# Output.net
KiCad netlist of a schematic drawn in Altium Designer
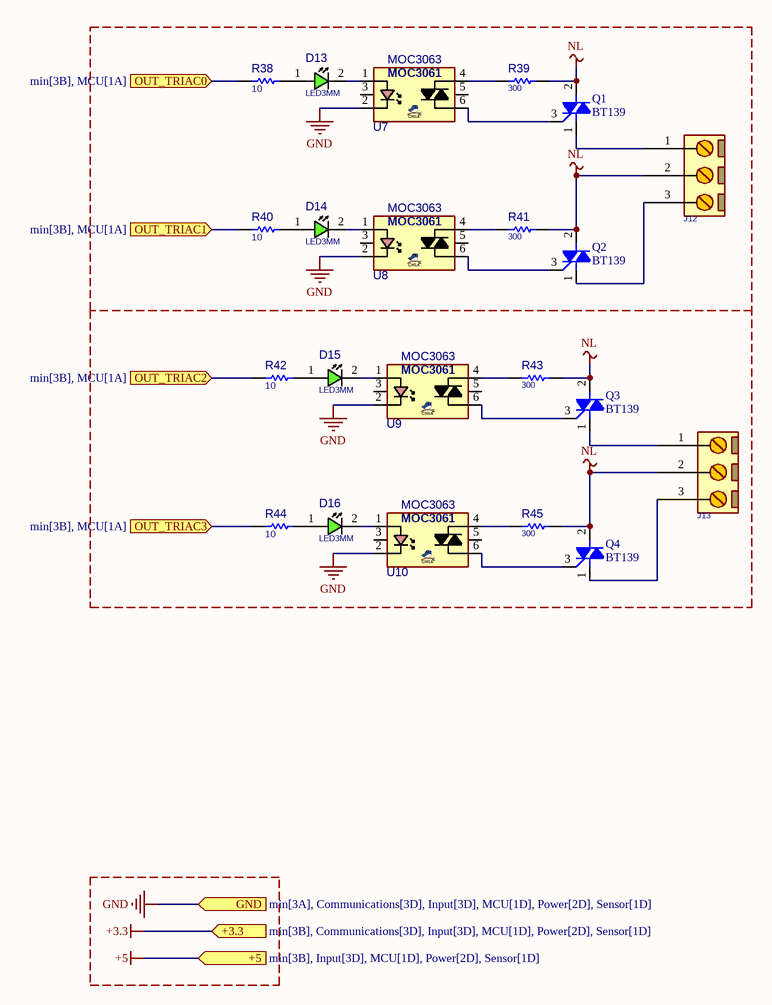
[diagram p0: Output.SchDoc]

(export (version "E")
  (design (tool "Eeschema 10.0.6"))
  (components
    (comp (ref "D13")
      (value "LED3MM")
      (footprint "LED3MM")
      (description "LED, THD, 3MM, GREEN")
      (fields (field (name "MANF") "MANF") (field (name "MANF_P#") "MANF_PART#"))
      (libsource (lib "led(diode)") (part "LED_THD_3MM"))
    )
    (comp (ref "D14")
      (value "LED3MM")
      (footprint "LED3MM")
      (description "LED, THD, 3MM, GREEN")
      (fields (field (name "MANF") "MANF") (field (name "MANF_P#") "MANF_PART#"))
      (libsource (lib "led(diode)") (part "LED_THD_3MM"))
    )
    (comp (ref "D15")
      (value "LED3MM")
      (footprint "LED3MM")
      (description "LED, THD, 3MM, GREEN")
      (fields (field (name "MANF") "MANF") (field (name "MANF_P#") "MANF_PART#"))
      (libsource (lib "led(diode)") (part "LED_THD_3MM"))
    )
    (comp (ref "D16")
      (value "LED3MM")
      (footprint "LED3MM")
      (description "LED, THD, 3MM, GREEN")
      (fields (field (name "MANF") "MANF") (field (name "MANF_P#") "MANF_PART#"))
      (libsource (lib "led(diode)") (part "LED_THD_3MM"))
    )
    (comp (ref "J12")
      (value "CONN_GMSTB3")
      (footprint "GMSTB762_3")
      (description "CONN, PHOENIX MSTB, 5-G, 5.08mm pitch")
      (fields (field (name "MANF_P#") "GMSTB 2,5/3-G-7,62"))
      (libsource (lib "conn_terminalB") (part "CONN_GMSTB762_3"))
    )
    (comp (ref "J13")
      (value "CONN_GMSTB3")
      (footprint "GMSTB762_3")
      (description "CONN, PHOENIX MSTB, 5-G, 5.08mm pitch")
      (fields (field (name "MANF_P#") "GMSTB 2,5/3-G-7,62"))
      (libsource (lib "conn_terminalB") (part "CONN_GMSTB762_3"))
    )
    (comp (ref "Q1")
      (value "BT139")
      (footprint "TO220_3")
      (description "Triac, 600V, 4A, TO-220, Silicon Bidirectional Thyristor")
      (libsource (lib "triac_diac") (part "TRIAC"))
    )
    (comp (ref "Q2")
      (value "BT139")
      (footprint "TO220_3")
      (description "Triac, 600V, 4A, TO-220, Silicon Bidirectional Thyristor")
      (libsource (lib "triac_diac") (part "TRIAC"))
    )
    (comp (ref "Q3")
      (value "BT139")
      (footprint "TO220_3")
      (description "Triac, 600V, 4A, TO-220, Silicon Bidirectional Thyristor")
      (libsource (lib "triac_diac") (part "TRIAC"))
    )
    (comp (ref "Q4")
      (value "BT139")
      (footprint "TO220_3")
      (description "Triac, 600V, 4A, TO-220, Silicon Bidirectional Thyristor")
      (libsource (lib "triac_diac") (part "TRIAC"))
    )
    (comp (ref "R38")
      (value "10")
      (footprint "R1206")
      (description "RESISTOR, SMD")
      (libsource (lib "passive_smd") (part "RES_SMD"))
    )
    (comp (ref "R39")
      (value "300")
      (footprint "R025W_AX_VER")
      (description "RESISTOR, THD")
      (fields (field (name "MANF_P#") "RK73H1ETTP4701F") (field (name "MANF") "KOA SPEER"))
      (libsource (lib "passive_thd") (part "RES_THD"))
    )
    (comp (ref "R40")
      (value "10")
      (footprint "R1206")
      (description "RESISTOR, SMD")
      (libsource (lib "passive_smd") (part "RES_SMD"))
    )
    (comp (ref "R41")
      (value "300")
      (footprint "R025W_AX_VER")
      (description "RESISTOR, THD")
      (fields (field (name "MANF_P#") "RK73H1ETTP4701F") (field (name "MANF") "KOA SPEER"))
      (libsource (lib "passive_thd") (part "RES_THD"))
    )
    (comp (ref "R42")
      (value "10")
      (footprint "R1206")
      (description "RESISTOR, SMD")
      (libsource (lib "passive_smd") (part "RES_SMD"))
    )
    (comp (ref "R43")
      (value "300")
      (footprint "R025W_AX_VER")
      (description "RESISTOR, THD")
      (fields (field (name "MANF_P#") "RK73H1ETTP4701F") (field (name "MANF") "KOA SPEER"))
      (libsource (lib "passive_thd") (part "RES_THD"))
    )
    (comp (ref "R44")
      (value "10")
      (footprint "R1206")
      (description "RESISTOR, SMD")
      (libsource (lib "passive_smd") (part "RES_SMD"))
    )
    (comp (ref "R45")
      (value "300")
      (footprint "R025W_AX_VER")
      (description "RESISTOR, THD")
      (fields (field (name "MANF_P#") "RK73H1ETTP4701F") (field (name "MANF") "KOA SPEER"))
      (libsource (lib "passive_thd") (part "RES_THD"))
    )
    (comp (ref "U7")
      (value "MOC3063")
      (footprint "DIP_6")
      (description "OPTOTRIAC, 600v/1A, 6v In")
      (fields (field (name "MANF_P#") "MOC3061"))
      (libsource (lib "optocoupler") (part "OPT_TRIAC6P_MOC3061"))
    )
    (comp (ref "U8")
      (value "MOC3063")
      (footprint "DIP_6")
      (description "OPTOTRIAC, 600v/1A, 6v In")
      (fields (field (name "MANF_P#") "MOC3061"))
      (libsource (lib "optocoupler") (part "OPT_TRIAC6P_MOC3061"))
    )
    (comp (ref "U9")
      (value "MOC3063")
      (footprint "DIP_6")
      (description "OPTOTRIAC, 600v/1A, 6v In")
      (fields (field (name "MANF_P#") "MOC3061"))
      (libsource (lib "optocoupler") (part "OPT_TRIAC6P_MOC3061"))
    )
    (comp (ref "U10")
      (value "MOC3063")
      (footprint "DIP_6")
      (description "OPTOTRIAC, 600v/1A, 6v In")
      (fields (field (name "MANF_P#") "MOC3061"))
      (libsource (lib "optocoupler") (part "OPT_TRIAC6P_MOC3061"))
    )
  )
  (nets
    (net (code "3") (name "/OUT_TRIAC0") (class "Default")
      (node (ref "R38") (pin "1") (pinfunction "1_1") (pintype "passive"))
    )
    (net (code "4") (name "/OUT_TRIAC1") (class "Default")
      (node (ref "R40") (pin "1") (pinfunction "1_1") (pintype "passive"))
    )
    (net (code "5") (name "/OUT_TRIAC2") (class "Default")
      (node (ref "R42") (pin "1") (pinfunction "1_1") (pintype "passive"))
    )
    (net (code "6") (name "/OUT_TRIAC3") (class "Default")
      (node (ref "R44") (pin "1") (pinfunction "1_1") (pintype "passive"))
    )
    (net (code "7") (name "GND") (class "Default")
      (node (ref "U10") (pin "2") (pinfunction "K_2") (pintype "passive"))
      (node (ref "U7") (pin "2") (pinfunction "K_2") (pintype "passive"))
      (node (ref "U8") (pin "2") (pinfunction "K_2") (pintype "passive"))
      (node (ref "U9") (pin "2") (pinfunction "K_2") (pintype "passive"))
    )
    (net (code "8") (name "NL") (class "Default")
      (node (ref "J12") (pin "2") (pinfunction "2_2") (pintype "passive"))
      (node (ref "J13") (pin "2") (pinfunction "2_2") (pintype "passive"))
      (node (ref "Q1") (pin "2") (pinfunction "T2_2") (pintype "passive"))
      (node (ref "Q2") (pin "2") (pinfunction "T2_2") (pintype "passive"))
      (node (ref "Q3") (pin "2") (pinfunction "T2_2") (pintype "passive"))
      (node (ref "Q4") (pin "2") (pinfunction "T2_2") (pintype "passive"))
      (node (ref "R39") (pin "2") (pinfunction "2_2") (pintype "passive"))
      (node (ref "R41") (pin "2") (pinfunction "2_2") (pintype "passive"))
      (node (ref "R43") (pin "2") (pinfunction "2_2") (pintype "passive"))
      (node (ref "R45") (pin "2") (pinfunction "2_2") (pintype "passive"))
    )
    (net (code "9") (name "Net-(D13-ANODE)") (class "Default")
      (node (ref "D13") (pin "1") (pinfunction "ANODE_1") (pintype "passive"))
      (node (ref "R38") (pin "2") (pinfunction "2_2") (pintype "passive"))
    )
    (net (code "10") (name "Net-(D13-CATHODE)") (class "Default")
      (node (ref "D13") (pin "2") (pinfunction "CATHODE_2") (pintype "passive"))
      (node (ref "U7") (pin "1") (pinfunction "A_1") (pintype "passive"))
    )
    (net (code "11") (name "Net-(D14-ANODE)") (class "Default")
      (node (ref "D14") (pin "1") (pinfunction "ANODE_1") (pintype "passive"))
      (node (ref "R40") (pin "2") (pinfunction "2_2") (pintype "passive"))
    )
    (net (code "12") (name "Net-(D14-CATHODE)") (class "Default")
      (node (ref "D14") (pin "2") (pinfunction "CATHODE_2") (pintype "passive"))
      (node (ref "U8") (pin "1") (pinfunction "A_1") (pintype "passive"))
    )
    (net (code "13") (name "Net-(D15-ANODE)") (class "Default")
      (node (ref "D15") (pin "1") (pinfunction "ANODE_1") (pintype "passive"))
      (node (ref "R42") (pin "2") (pinfunction "2_2") (pintype "passive"))
    )
    (net (code "14") (name "Net-(D15-CATHODE)") (class "Default")
      (node (ref "D15") (pin "2") (pinfunction "CATHODE_2") (pintype "passive"))
      (node (ref "U9") (pin "1") (pinfunction "A_1") (pintype "passive"))
    )
    (net (code "15") (name "Net-(D16-ANODE)") (class "Default")
      (node (ref "D16") (pin "1") (pinfunction "ANODE_1") (pintype "passive"))
      (node (ref "R44") (pin "2") (pinfunction "2_2") (pintype "passive"))
    )
    (net (code "16") (name "Net-(D16-CATHODE)") (class "Default")
      (node (ref "D16") (pin "2") (pinfunction "CATHODE_2") (pintype "passive"))
      (node (ref "U10") (pin "1") (pinfunction "A_1") (pintype "passive"))
    )
    (net (code "17") (name "Net-(Q1-G)") (class "Default")
      (node (ref "Q1") (pin "3") (pinfunction "G_3") (pintype "passive"))
      (node (ref "U7") (pin "6") (pinfunction "A/K_6") (pintype "passive"))
    )
    (net (code "18") (name "Net-(Q1-T1)") (class "Default")
      (node (ref "J12") (pin "1") (pinfunction "1_1") (pintype "passive"))
      (node (ref "Q1") (pin "1") (pinfunction "T1_1") (pintype "passive"))
    )
    (net (code "19") (name "Net-(Q2-G)") (class "Default")
      (node (ref "Q2") (pin "3") (pinfunction "G_3") (pintype "passive"))
      (node (ref "U8") (pin "6") (pinfunction "A/K_6") (pintype "passive"))
    )
    (net (code "20") (name "Net-(Q2-T1)") (class "Default")
      (node (ref "J12") (pin "3") (pinfunction "3_3") (pintype "passive"))
      (node (ref "Q2") (pin "1") (pinfunction "T1_1") (pintype "passive"))
    )
    (net (code "21") (name "Net-(Q3-G)") (class "Default")
      (node (ref "Q3") (pin "3") (pinfunction "G_3") (pintype "passive"))
      (node (ref "U9") (pin "6") (pinfunction "A/K_6") (pintype "passive"))
    )
    (net (code "22") (name "Net-(Q3-T1)") (class "Default")
      (node (ref "J13") (pin "1") (pinfunction "1_1") (pintype "passive"))
      (node (ref "Q3") (pin "1") (pinfunction "T1_1") (pintype "passive"))
    )
    (net (code "23") (name "Net-(Q4-G)") (class "Default")
      (node (ref "Q4") (pin "3") (pinfunction "G_3") (pintype "passive"))
      (node (ref "U10") (pin "6") (pinfunction "A/K_6") (pintype "passive"))
    )
    (net (code "24") (name "Net-(Q4-T1)") (class "Default")
      (node (ref "J13") (pin "3") (pinfunction "3_3") (pintype "passive"))
      (node (ref "Q4") (pin "1") (pinfunction "T1_1") (pintype "passive"))
    )
    (net (code "25") (name "Net-(R39-Pad1)") (class "Default")
      (node (ref "R39") (pin "1") (pinfunction "1_1") (pintype "passive"))
      (node (ref "U7") (pin "4") (pinfunction "A/K_4") (pintype "passive"))
    )
    (net (code "26") (name "Net-(R41-Pad1)") (class "Default")
      (node (ref "R41") (pin "1") (pinfunction "1_1") (pintype "passive"))
      (node (ref "U8") (pin "4") (pinfunction "A/K_4") (pintype "passive"))
    )
    (net (code "27") (name "Net-(R43-Pad1)") (class "Default")
      (node (ref "R43") (pin "1") (pinfunction "1_1") (pintype "passive"))
      (node (ref "U9") (pin "4") (pinfunction "A/K_4") (pintype "passive"))
    )
    (net (code "28") (name "Net-(R45-Pad1)") (class "Default")
      (node (ref "R45") (pin "1") (pinfunction "1_1") (pintype "passive"))
      (node (ref "U10") (pin "4") (pinfunction "A/K_4") (pintype "passive"))
    )
    (net (code "29") (name "unconnected-(U7-NC-Pad3)") (class "Default")
      (node (ref "U7") (pin "3") (pinfunction "NC_3") (pintype "passive"))
    )
    (net (code "30") (name "unconnected-(U7-NC-Pad5)") (class "Default")
      (node (ref "U7") (pin "5") (pinfunction "NC_5") (pintype "passive"))
    )
    (net (code "31") (name "unconnected-(U8-NC-Pad3)") (class "Default")
      (node (ref "U8") (pin "3") (pinfunction "NC_3") (pintype "passive"))
    )
    (net (code "32") (name "unconnected-(U8-NC-Pad5)") (class "Default")
      (node (ref "U8") (pin "5") (pinfunction "NC_5") (pintype "passive"))
    )
    (net (code "33") (name "unconnected-(U9-NC-Pad3)") (class "Default")
      (node (ref "U9") (pin "3") (pinfunction "NC_3") (pintype "passive"))
    )
    (net (code "34") (name "unconnected-(U9-NC-Pad5)") (class "Default")
      (node (ref "U9") (pin "5") (pinfunction "NC_5") (pintype "passive"))
    )
    (net (code "35") (name "unconnected-(U10-NC-Pad3)") (class "Default")
      (node (ref "U10") (pin "3") (pinfunction "NC_3") (pintype "passive"))
    )
    (net (code "36") (name "unconnected-(U10-NC-Pad5)") (class "Default")
      (node (ref "U10") (pin "5") (pinfunction "NC_5") (pintype "passive"))
    )
  )
)
